# Schematic.net
KiCad netlist of a schematic drawn in Altium Designer
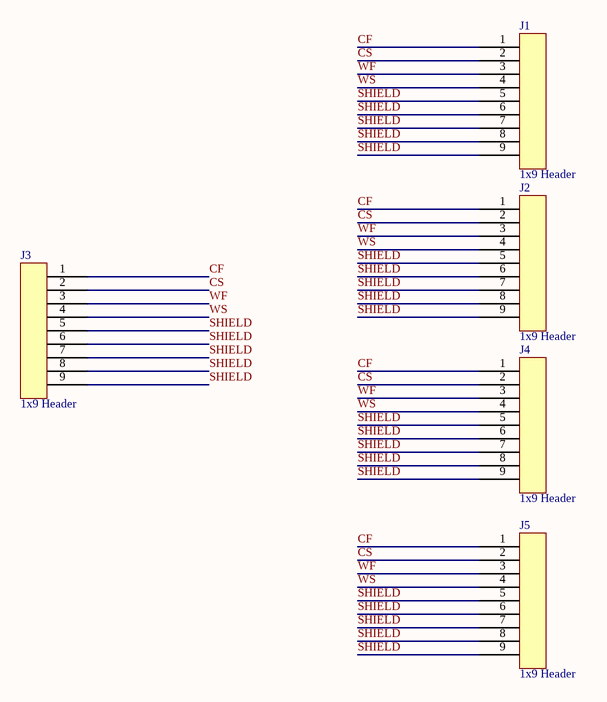
[diagram p0: Schematic.SchDoc]

(export (version "E")
  (design (tool "Eeschema 10.0.6"))
  (components
    (comp (ref "J1")
      (value "1x9 Header")
      (footprint "D-SUB-9PIN-TE")
      (libsource (lib "Schematic_Components") (part "1x9 Header"))
    )
    (comp (ref "J2")
      (value "1x9 Header")
      (footprint "D-SUB-9PIN-TE")
      (libsource (lib "Schematic_Components") (part "1x9 Header"))
    )
    (comp (ref "J3")
      (value "1x9 Header")
      (footprint "D-SUB-9PIN-TE")
      (libsource (lib "") (part "1x9 Header_1"))
    )
    (comp (ref "J4")
      (value "1x9 Header")
      (footprint "D-SUB-9PIN-TE")
      (libsource (lib "Schematic_Components") (part "1x9 Header"))
    )
    (comp (ref "J5")
      (value "1x9 Header")
      (footprint "D-SUB-9PIN-TE")
      (libsource (lib "Schematic_Components") (part "1x9 Header"))
    )
  )
  (nets
    (net (code "1") (name "/CF") (class "Default")
      (node (ref "J1") (pin "1") (pintype "passive"))
      (node (ref "J2") (pin "1") (pintype "passive"))
      (node (ref "J3") (pin "1") (pintype "passive"))
      (node (ref "J4") (pin "1") (pintype "passive"))
      (node (ref "J5") (pin "1") (pintype "passive"))
    )
    (net (code "2") (name "/CS") (class "Default")
      (node (ref "J1") (pin "2") (pintype "passive"))
      (node (ref "J2") (pin "2") (pintype "passive"))
      (node (ref "J3") (pin "2") (pintype "passive"))
      (node (ref "J4") (pin "2") (pintype "passive"))
      (node (ref "J5") (pin "2") (pintype "passive"))
    )
    (net (code "3") (name "/SHIELD") (class "Default")
      (node (ref "J1") (pin "5") (pintype "passive"))
      (node (ref "J1") (pin "6") (pintype "passive"))
      (node (ref "J1") (pin "7") (pintype "passive"))
      (node (ref "J1") (pin "8") (pintype "passive"))
      (node (ref "J1") (pin "9") (pintype "passive"))
      (node (ref "J2") (pin "5") (pintype "passive"))
      (node (ref "J2") (pin "6") (pintype "passive"))
      (node (ref "J2") (pin "7") (pintype "passive"))
      (node (ref "J2") (pin "8") (pintype "passive"))
      (node (ref "J2") (pin "9") (pintype "passive"))
      (node (ref "J3") (pin "5") (pintype "passive"))
      (node (ref "J3") (pin "6") (pintype "passive"))
      (node (ref "J3") (pin "7") (pintype "passive"))
      (node (ref "J3") (pin "8") (pintype "passive"))
      (node (ref "J3") (pin "9") (pintype "passive"))
      (node (ref "J4") (pin "5") (pintype "passive"))
      (node (ref "J4") (pin "6") (pintype "passive"))
      (node (ref "J4") (pin "7") (pintype "passive"))
      (node (ref "J4") (pin "8") (pintype "passive"))
      (node (ref "J4") (pin "9") (pintype "passive"))
      (node (ref "J5") (pin "5") (pintype "passive"))
      (node (ref "J5") (pin "6") (pintype "passive"))
      (node (ref "J5") (pin "7") (pintype "passive"))
      (node (ref "J5") (pin "8") (pintype "passive"))
      (node (ref "J5") (pin "9") (pintype "passive"))
    )
    (net (code "4") (name "/WF") (class "Default")
      (node (ref "J1") (pin "3") (pintype "passive"))
      (node (ref "J2") (pin "3") (pintype "passive"))
      (node (ref "J3") (pin "3") (pintype "passive"))
      (node (ref "J4") (pin "3") (pintype "passive"))
      (node (ref "J5") (pin "3") (pintype "passive"))
    )
    (net (code "5") (name "/WS") (class "Default")
      (node (ref "J1") (pin "4") (pintype "passive"))
      (node (ref "J2") (pin "4") (pintype "passive"))
      (node (ref "J3") (pin "4") (pintype "passive"))
      (node (ref "J4") (pin "4") (pintype "passive"))
      (node (ref "J5") (pin "4") (pintype "passive"))
    )
  )
)
